# ExtensionConnector.net
KiCad netlist of a schematic drawn in Altium Designer
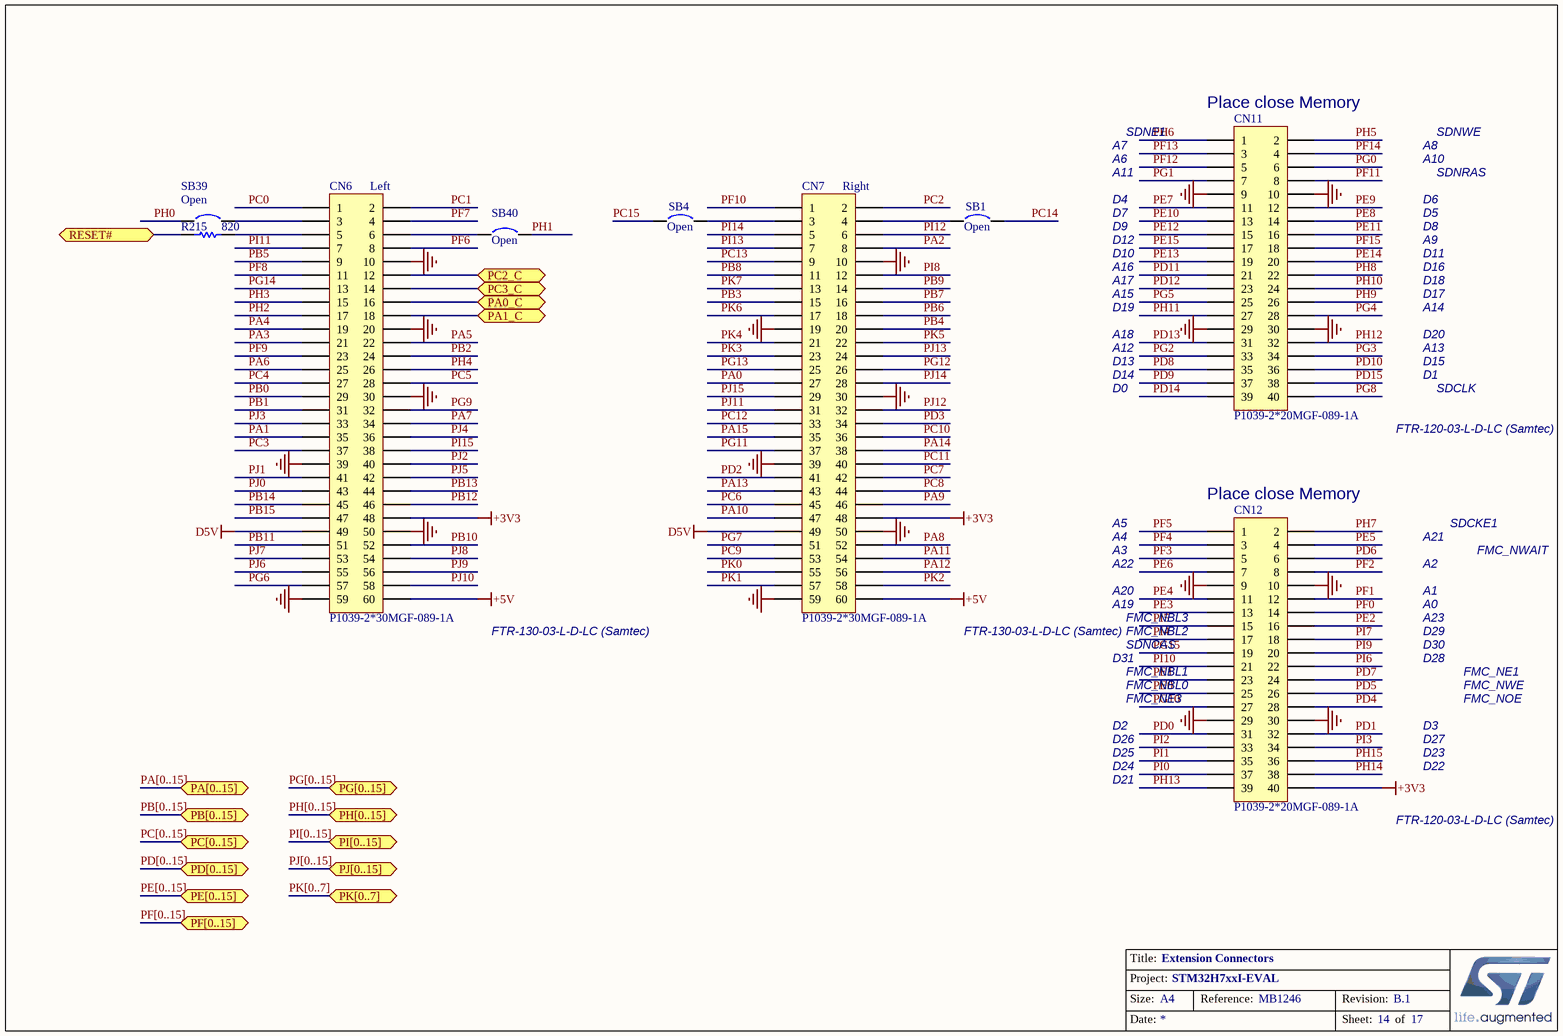
[diagram p0: ExtensionConnector.SchDoc]

(export (version "E")
  (design (tool "Eeschema 10.0.6"))
  (components
    (comp (ref "CN6")
      (value "P1039-2*30MGF-089-1A")
      (footprint "FTR-130-53-L-D-LC")
      (description "Header, 40-Pin, Dual row")
      (fields (field (name "PUBLISHER") "Altium Limited"))
      (libsource (lib "mb1045") (part "FTR-130-53-L-D-LC"))
    )
    (comp (ref "CN7")
      (value "P1039-2*30MGF-089-1A")
      (footprint "FTR-130-53-L-D-LC")
      (description "Header, 40-Pin, Dual row")
      (fields (field (name "PUBLISHER") "Altium Limited"))
      (libsource (lib "mb1045") (part "FTR-130-53-L-D-LC"))
    )
    (comp (ref "CN11")
      (value "P1039-2*20MGF-089-1A")
      (footprint "FTR-120-53-L-D-LC")
      (description "Header, 20-Pin, Dual row")
      (fields (field (name "PUBLISHER") "Altium Limited"))
      (libsource (lib "mb1045") (part "FTR-120-53-L-D-LC"))
    )
    (comp (ref "CN12")
      (value "P1039-2*20MGF-089-1A")
      (footprint "FTR-120-53-L-D-LC")
      (description "Header, 20-Pin, Dual row")
      (fields (field (name "PUBLISHER") "Altium Limited"))
      (libsource (lib "mb1045") (part "FTR-120-53-L-D-LC"))
    )
    (comp (ref "R215")
      (value "820")
      (footprint "0603R")
      (description "Resistor")
      (fields (field (name "PUBLISHER") "Altium Limited"))
      (libsource (lib "Miscellaneous Devices") (part "res1"))
    )
    (comp (ref "SB1")
      (value "Open")
      (footprint "0402R")
      (description "Circuit Breaker")
      (fields (field (name "PUBLISHER") "Altium Limited"))
      (libsource (lib "MB1167") (part "Circuit Breaker"))
    )
    (comp (ref "SB4")
      (value "Open")
      (footprint "0402R")
      (description "Circuit Breaker")
      (fields (field (name "PUBLISHER") "Altium Limited"))
      (libsource (lib "") (part "Circuit Breaker_1"))
    )
    (comp (ref "SB39")
      (value "Open")
      (footprint "SB_0603")
      (description "Circuit Breaker")
      (fields (field (name "PUBLISHER") "Altium Limited"))
      (libsource (lib "") (part "Circuit Breaker_1"))
    )
    (comp (ref "SB40")
      (value "Open")
      (footprint "SB_0603")
      (description "Circuit Breaker")
      (fields (field (name "PUBLISHER") "Altium Limited"))
      (libsource (lib "MB1167") (part "Circuit Breaker"))
    )
  )
  (nets
    (net (code "1") (name "+3V3") (class "Default")
      (node (ref "CN12") (pin "40") (pinfunction "40_40") (pintype "passive"))
      (node (ref "CN6") (pin "48") (pinfunction "48_48") (pintype "passive"))
      (node (ref "CN7") (pin "48") (pinfunction "48_48") (pintype "passive"))
    )
    (net (code "2") (name "+5V") (class "Default")
      (node (ref "CN6") (pin "60") (pinfunction "60_60") (pintype "passive"))
      (node (ref "CN7") (pin "60") (pinfunction "60_60") (pintype "passive"))
    )
    (net (code "3") (name "/PA0") (class "Default")
      (node (ref "CN7") (pin "27") (pinfunction "27_27") (pintype "passive"))
    )
    (net (code "4") (name "/PA0_C") (class "Default")
      (node (ref "CN6") (pin "16") (pinfunction "16_16") (pintype "passive"))
    )
    (net (code "5") (name "/PA1") (class "Default")
      (node (ref "CN6") (pin "35") (pinfunction "35_35") (pintype "passive"))
    )
    (net (code "6") (name "/PA1_C") (class "Default")
      (node (ref "CN6") (pin "18") (pinfunction "18_18") (pintype "passive"))
    )
    (net (code "7") (name "/PA2") (class "Default")
      (node (ref "CN7") (pin "8") (pinfunction "8_8") (pintype "passive"))
    )
    (net (code "8") (name "/PA3") (class "Default")
      (node (ref "CN6") (pin "21") (pinfunction "21_21") (pintype "passive"))
    )
    (net (code "9") (name "/PA4") (class "Default")
      (node (ref "CN6") (pin "19") (pinfunction "19_19") (pintype "passive"))
    )
    (net (code "10") (name "/PA5") (class "Default")
      (node (ref "CN6") (pin "22") (pinfunction "22_22") (pintype "passive"))
    )
    (net (code "11") (name "/PA6") (class "Default")
      (node (ref "CN6") (pin "25") (pinfunction "25_25") (pintype "passive"))
    )
    (net (code "12") (name "/PA7") (class "Default")
      (node (ref "CN6") (pin "34") (pinfunction "34_34") (pintype "passive"))
    )
    (net (code "13") (name "/PA8") (class "Default")
      (node (ref "CN7") (pin "52") (pinfunction "52_52") (pintype "passive"))
    )
    (net (code "14") (name "/PA9") (class "Default")
      (node (ref "CN7") (pin "46") (pinfunction "46_46") (pintype "passive"))
    )
    (net (code "15") (name "/PA10") (class "Default")
      (node (ref "CN7") (pin "47") (pinfunction "47_47") (pintype "passive"))
    )
    (net (code "16") (name "/PA11") (class "Default")
      (node (ref "CN7") (pin "54") (pinfunction "54_54") (pintype "passive"))
    )
    (net (code "17") (name "/PA12") (class "Default")
      (node (ref "CN7") (pin "56") (pinfunction "56_56") (pintype "passive"))
    )
    (net (code "18") (name "/PA13") (class "Default")
      (node (ref "CN7") (pin "43") (pinfunction "43_43") (pintype "passive"))
    )
    (net (code "19") (name "/PA14") (class "Default")
      (node (ref "CN7") (pin "38") (pinfunction "38_38") (pintype "passive"))
    )
    (net (code "20") (name "/PA15") (class "Default")
      (node (ref "CN7") (pin "35") (pinfunction "35_35") (pintype "passive"))
    )
    (net (code "22") (name "/PB0") (class "Default")
      (node (ref "CN6") (pin "29") (pinfunction "29_29") (pintype "passive"))
    )
    (net (code "23") (name "/PB1") (class "Default")
      (node (ref "CN6") (pin "31") (pinfunction "31_31") (pintype "passive"))
    )
    (net (code "24") (name "/PB2") (class "Default")
      (node (ref "CN6") (pin "24") (pinfunction "24_24") (pintype "passive"))
    )
    (net (code "25") (name "/PB3") (class "Default")
      (node (ref "CN7") (pin "15") (pinfunction "15_15") (pintype "passive"))
    )
    (net (code "26") (name "/PB4") (class "Default")
      (node (ref "CN7") (pin "20") (pinfunction "20_20") (pintype "passive"))
    )
    (net (code "27") (name "/PB5") (class "Default")
      (node (ref "CN6") (pin "9") (pinfunction "9_9") (pintype "passive"))
    )
    (net (code "28") (name "/PB6") (class "Default")
      (node (ref "CN7") (pin "18") (pinfunction "18_18") (pintype "passive"))
    )
    (net (code "29") (name "/PB7") (class "Default")
      (node (ref "CN7") (pin "16") (pinfunction "16_16") (pintype "passive"))
    )
    (net (code "30") (name "/PB8") (class "Default")
      (node (ref "CN7") (pin "11") (pinfunction "11_11") (pintype "passive"))
    )
    (net (code "31") (name "/PB9") (class "Default")
      (node (ref "CN7") (pin "14") (pinfunction "14_14") (pintype "passive"))
    )
    (net (code "32") (name "/PB10") (class "Default")
      (node (ref "CN6") (pin "52") (pinfunction "52_52") (pintype "passive"))
    )
    (net (code "33") (name "/PB11") (class "Default")
      (node (ref "CN6") (pin "51") (pinfunction "51_51") (pintype "passive"))
    )
    (net (code "34") (name "/PB12") (class "Default")
      (node (ref "CN6") (pin "46") (pinfunction "46_46") (pintype "passive"))
    )
    (net (code "35") (name "/PB13") (class "Default")
      (node (ref "CN6") (pin "44") (pinfunction "44_44") (pintype "passive"))
    )
    (net (code "36") (name "/PB14") (class "Default")
      (node (ref "CN6") (pin "45") (pinfunction "45_45") (pintype "passive"))
    )
    (net (code "37") (name "/PB15") (class "Default")
      (node (ref "CN6") (pin "47") (pinfunction "47_47") (pintype "passive"))
    )
    (net (code "39") (name "/PC0") (class "Default")
      (node (ref "CN6") (pin "1") (pinfunction "1_1") (pintype "passive"))
    )
    (net (code "40") (name "/PC1") (class "Default")
      (node (ref "CN6") (pin "2") (pinfunction "2_2") (pintype "passive"))
    )
    (net (code "41") (name "/PC2") (class "Default")
      (node (ref "CN7") (pin "2") (pinfunction "2_2") (pintype "passive"))
    )
    (net (code "42") (name "/PC2_C") (class "Default")
      (node (ref "CN6") (pin "12") (pinfunction "12_12") (pintype "passive"))
    )
    (net (code "43") (name "/PC3") (class "Default")
      (node (ref "CN6") (pin "37") (pinfunction "37_37") (pintype "passive"))
    )
    (net (code "44") (name "/PC3_C") (class "Default")
      (node (ref "CN6") (pin "14") (pinfunction "14_14") (pintype "passive"))
    )
    (net (code "45") (name "/PC4") (class "Default")
      (node (ref "CN6") (pin "27") (pinfunction "27_27") (pintype "passive"))
    )
    (net (code "46") (name "/PC5") (class "Default")
      (node (ref "CN6") (pin "28") (pinfunction "28_28") (pintype "passive"))
    )
    (net (code "47") (name "/PC6") (class "Default")
      (node (ref "CN7") (pin "45") (pinfunction "45_45") (pintype "passive"))
    )
    (net (code "48") (name "/PC7") (class "Default")
      (node (ref "CN7") (pin "42") (pinfunction "42_42") (pintype "passive"))
    )
    (net (code "49") (name "/PC8") (class "Default")
      (node (ref "CN7") (pin "44") (pinfunction "44_44") (pintype "passive"))
    )
    (net (code "50") (name "/PC9") (class "Default")
      (node (ref "CN7") (pin "53") (pinfunction "53_53") (pintype "passive"))
    )
    (net (code "51") (name "/PC10") (class "Default")
      (node (ref "CN7") (pin "36") (pinfunction "36_36") (pintype "passive"))
    )
    (net (code "52") (name "/PC11") (class "Default")
      (node (ref "CN7") (pin "40") (pinfunction "40_40") (pintype "passive"))
    )
    (net (code "53") (name "/PC12") (class "Default")
      (node (ref "CN7") (pin "33") (pinfunction "33_33") (pintype "passive"))
    )
    (net (code "54") (name "/PC13") (class "Default")
      (node (ref "CN7") (pin "9") (pinfunction "9_9") (pintype "passive"))
    )
    (net (code "55") (name "/PC14") (class "Default")
      (node (ref "SB1") (pin "1") (pinfunction "1_1") (pintype "passive"))
    )
    (net (code "56") (name "/PC15") (class "Default")
      (node (ref "SB4") (pin "1") (pinfunction "1_1") (pintype "passive"))
    )
    (net (code "58") (name "/PD0") (class "Default")
      (node (ref "CN12") (pin "31") (pinfunction "31_31") (pintype "passive"))
    )
    (net (code "59") (name "/PD1") (class "Default")
      (node (ref "CN12") (pin "32") (pinfunction "32_32") (pintype "passive"))
    )
    (net (code "60") (name "/PD2") (class "Default")
      (node (ref "CN7") (pin "41") (pinfunction "41_41") (pintype "passive"))
    )
    (net (code "61") (name "/PD3") (class "Default")
      (node (ref "CN7") (pin "34") (pinfunction "34_34") (pintype "passive"))
    )
    (net (code "62") (name "/PD4") (class "Default")
      (node (ref "CN12") (pin "28") (pinfunction "28_28") (pintype "passive"))
    )
    (net (code "63") (name "/PD5") (class "Default")
      (node (ref "CN12") (pin "26") (pinfunction "26_26") (pintype "passive"))
    )
    (net (code "64") (name "/PD6") (class "Default")
      (node (ref "CN12") (pin "6") (pinfunction "6_6") (pintype "passive"))
    )
    (net (code "65") (name "/PD7") (class "Default")
      (node (ref "CN12") (pin "24") (pinfunction "24_24") (pintype "passive"))
    )
    (net (code "66") (name "/PD8") (class "Default")
      (node (ref "CN11") (pin "35") (pinfunction "35_35") (pintype "passive"))
    )
    (net (code "67") (name "/PD9") (class "Default")
      (node (ref "CN11") (pin "37") (pinfunction "37_37") (pintype "passive"))
    )
    (net (code "68") (name "/PD10") (class "Default")
      (node (ref "CN11") (pin "36") (pinfunction "36_36") (pintype "passive"))
    )
    (net (code "69") (name "/PD11") (class "Default")
      (node (ref "CN11") (pin "21") (pinfunction "21_21") (pintype "passive"))
    )
    (net (code "70") (name "/PD12") (class "Default")
      (node (ref "CN11") (pin "23") (pinfunction "23_23") (pintype "passive"))
    )
    (net (code "71") (name "/PD13") (class "Default")
      (node (ref "CN11") (pin "31") (pinfunction "31_31") (pintype "passive"))
    )
    (net (code "72") (name "/PD14") (class "Default")
      (node (ref "CN11") (pin "39") (pinfunction "39_39") (pintype "passive"))
    )
    (net (code "73") (name "/PD15") (class "Default")
      (node (ref "CN11") (pin "38") (pinfunction "38_38") (pintype "passive"))
    )
    (net (code "75") (name "/PE0") (class "Default")
      (node (ref "CN12") (pin "25") (pinfunction "25_25") (pintype "passive"))
    )
    (net (code "76") (name "/PE1") (class "Default")
      (node (ref "CN12") (pin "23") (pinfunction "23_23") (pintype "passive"))
    )
    (net (code "77") (name "/PE2") (class "Default")
      (node (ref "CN12") (pin "16") (pinfunction "16_16") (pintype "passive"))
    )
    (net (code "78") (name "/PE3") (class "Default")
      (node (ref "CN12") (pin "13") (pinfunction "13_13") (pintype "passive"))
    )
    (net (code "79") (name "/PE4") (class "Default")
      (node (ref "CN12") (pin "11") (pinfunction "11_11") (pintype "passive"))
    )
    (net (code "80") (name "/PE5") (class "Default")
      (node (ref "CN12") (pin "4") (pinfunction "4_4") (pintype "passive"))
    )
    (net (code "81") (name "/PE6") (class "Default")
      (node (ref "CN12") (pin "7") (pinfunction "7_7") (pintype "passive"))
    )
    (net (code "82") (name "/PE7") (class "Default")
      (node (ref "CN11") (pin "11") (pinfunction "11_11") (pintype "passive"))
    )
    (net (code "83") (name "/PE8") (class "Default")
      (node (ref "CN11") (pin "14") (pinfunction "14_14") (pintype "passive"))
    )
    (net (code "84") (name "/PE9") (class "Default")
      (node (ref "CN11") (pin "12") (pinfunction "12_12") (pintype "passive"))
    )
    (net (code "85") (name "/PE10") (class "Default")
      (node (ref "CN11") (pin "13") (pinfunction "13_13") (pintype "passive"))
    )
    (net (code "86") (name "/PE11") (class "Default")
      (node (ref "CN11") (pin "16") (pinfunction "16_16") (pintype "passive"))
    )
    (net (code "87") (name "/PE12") (class "Default")
      (node (ref "CN11") (pin "15") (pinfunction "15_15") (pintype "passive"))
    )
    (net (code "88") (name "/PE13") (class "Default")
      (node (ref "CN11") (pin "19") (pinfunction "19_19") (pintype "passive"))
    )
    (net (code "89") (name "/PE14") (class "Default")
      (node (ref "CN11") (pin "20") (pinfunction "20_20") (pintype "passive"))
    )
    (net (code "90") (name "/PE15") (class "Default")
      (node (ref "CN11") (pin "17") (pinfunction "17_17") (pintype "passive"))
    )
    (net (code "92") (name "/PF0") (class "Default")
      (node (ref "CN12") (pin "14") (pinfunction "14_14") (pintype "passive"))
    )
    (net (code "93") (name "/PF1") (class "Default")
      (node (ref "CN12") (pin "12") (pinfunction "12_12") (pintype "passive"))
    )
    (net (code "94") (name "/PF2") (class "Default")
      (node (ref "CN12") (pin "8") (pinfunction "8_8") (pintype "passive"))
    )
    (net (code "95") (name "/PF3") (class "Default")
      (node (ref "CN12") (pin "5") (pinfunction "5_5") (pintype "passive"))
    )
    (net (code "96") (name "/PF4") (class "Default")
      (node (ref "CN12") (pin "3") (pinfunction "3_3") (pintype "passive"))
    )
    (net (code "97") (name "/PF5") (class "Default")
      (node (ref "CN12") (pin "1") (pinfunction "1_1") (pintype "passive"))
    )
    (net (code "98") (name "/PF6") (class "Default")
      (node (ref "CN6") (pin "8") (pinfunction "8_8") (pintype "passive"))
    )
    (net (code "99") (name "/PF7") (class "Default")
      (node (ref "CN6") (pin "4") (pinfunction "4_4") (pintype "passive"))
    )
    (net (code "100") (name "/PF8") (class "Default")
      (node (ref "CN6") (pin "11") (pinfunction "11_11") (pintype "passive"))
    )
    (net (code "101") (name "/PF9") (class "Default")
      (node (ref "CN6") (pin "23") (pinfunction "23_23") (pintype "passive"))
    )
    (net (code "102") (name "/PF10") (class "Default")
      (node (ref "CN7") (pin "1") (pinfunction "1_1") (pintype "passive"))
    )
    (net (code "103") (name "/PF11") (class "Default")
      (node (ref "CN11") (pin "8") (pinfunction "8_8") (pintype "passive"))
    )
    (net (code "104") (name "/PF12") (class "Default")
      (node (ref "CN11") (pin "5") (pinfunction "5_5") (pintype "passive"))
    )
    (net (code "105") (name "/PF13") (class "Default")
      (node (ref "CN11") (pin "3") (pinfunction "3_3") (pintype "passive"))
    )
    (net (code "106") (name "/PF14") (class "Default")
      (node (ref "CN11") (pin "4") (pinfunction "4_4") (pintype "passive"))
    )
    (net (code "107") (name "/PF15") (class "Default")
      (node (ref "CN11") (pin "18") (pinfunction "18_18") (pintype "passive"))
    )
    (net (code "109") (name "/PG0") (class "Default")
      (node (ref "CN11") (pin "6") (pinfunction "6_6") (pintype "passive"))
    )
    (net (code "110") (name "/PG1") (class "Default")
      (node (ref "CN11") (pin "7") (pinfunction "7_7") (pintype "passive"))
    )
    (net (code "111") (name "/PG2") (class "Default")
      (node (ref "CN11") (pin "33") (pinfunction "33_33") (pintype "passive"))
    )
    (net (code "112") (name "/PG3") (class "Default")
      (node (ref "CN11") (pin "34") (pinfunction "34_34") (pintype "passive"))
    )
    (net (code "113") (name "/PG4") (class "Default")
      (node (ref "CN11") (pin "28") (pinfunction "28_28") (pintype "passive"))
    )
    (net (code "114") (name "/PG5") (class "Default")
      (node (ref "CN11") (pin "25") (pinfunction "25_25") (pintype "passive"))
    )
    (net (code "115") (name "/PG6") (class "Default")
      (node (ref "CN6") (pin "57") (pinfunction "57_57") (pintype "passive"))
    )
    (net (code "116") (name "/PG7") (class "Default")
      (node (ref "CN7") (pin "51") (pinfunction "51_51") (pintype "passive"))
    )
    (net (code "117") (name "/PG8") (class "Default")
      (node (ref "CN11") (pin "40") (pinfunction "40_40") (pintype "passive"))
    )
    (net (code "118") (name "/PG9") (class "Default")
      (node (ref "CN6") (pin "32") (pinfunction "32_32") (pintype "passive"))
    )
    (net (code "119") (name "/PG10") (class "Default")
      (node (ref "CN12") (pin "27") (pinfunction "27_27") (pintype "passive"))
    )
    (net (code "120") (name "/PG11") (class "Default")
      (node (ref "CN7") (pin "37") (pinfunction "37_37") (pintype "passive"))
    )
    (net (code "121") (name "/PG12") (class "Default")
      (node (ref "CN7") (pin "26") (pinfunction "26_26") (pintype "passive"))
    )
    (net (code "122") (name "/PG13") (class "Default")
      (node (ref "CN7") (pin "25") (pinfunction "25_25") (pintype "passive"))
    )
    (net (code "123") (name "/PG14") (class "Default")
      (node (ref "CN6") (pin "13") (pinfunction "13_13") (pintype "passive"))
    )
    (net (code "124") (name "/PG15") (class "Default")
      (node (ref "CN12") (pin "19") (pinfunction "19_19") (pintype "passive"))
    )
    (net (code "126") (name "/PH0") (class "Default")
      (node (ref "SB39") (pin "1") (pinfunction "1_1") (pintype "passive"))
    )
    (net (code "127") (name "/PH1") (class "Default")
      (node (ref "SB40") (pin "1") (pinfunction "1_1") (pintype "passive"))
    )
    (net (code "128") (name "/PH2") (class "Default")
      (node (ref "CN6") (pin "17") (pinfunction "17_17") (pintype "passive"))
    )
    (net (code "129") (name "/PH3") (class "Default")
      (node (ref "CN6") (pin "15") (pinfunction "15_15") (pintype "passive"))
    )
    (net (code "130") (name "/PH4") (class "Default")
      (node (ref "CN6") (pin "26") (pinfunction "26_26") (pintype "passive"))
    )
    (net (code "131") (name "/PH5") (class "Default")
      (node (ref "CN11") (pin "2") (pinfunction "2_2") (pintype "passive"))
    )
    (net (code "132") (name "/PH6") (class "Default")
      (node (ref "CN11") (pin "1") (pinfunction "1_1") (pintype "passive"))
    )
    (net (code "133") (name "/PH7") (class "Default")
      (node (ref "CN12") (pin "2") (pinfunction "2_2") (pintype "passive"))
    )
    (net (code "134") (name "/PH8") (class "Default")
      (node (ref "CN11") (pin "22") (pinfunction "22_22") (pintype "passive"))
    )
    (net (code "135") (name "/PH9") (class "Default")
      (node (ref "CN11") (pin "26") (pinfunction "26_26") (pintype "passive"))
    )
    (net (code "136") (name "/PH10") (class "Default")
      (node (ref "CN11") (pin "24") (pinfunction "24_24") (pintype "passive"))
    )
    (net (code "137") (name "/PH11") (class "Default")
      (node (ref "CN11") (pin "27") (pinfunction "27_27") (pintype "passive"))
    )
    (net (code "138") (name "/PH12") (class "Default")
      (node (ref "CN11") (pin "32") (pinfunction "32_32") (pintype "passive"))
    )
    (net (code "139") (name "/PH13") (class "Default")
      (node (ref "CN12") (pin "39") (pinfunction "39_39") (pintype "passive"))
    )
    (net (code "140") (name "/PH14") (class "Default")
      (node (ref "CN12") (pin "38") (pinfunction "38_38") (pintype "passive"))
    )
    (net (code "141") (name "/PH15") (class "Default")
      (node (ref "CN12") (pin "36") (pinfunction "36_36") (pintype "passive"))
    )
    (net (code "143") (name "/PI0") (class "Default")
      (node (ref "CN12") (pin "37") (pinfunction "37_37") (pintype "passive"))
    )
    (net (code "144") (name "/PI1") (class "Default")
      (node (ref "CN12") (pin "35") (pinfunction "35_35") (pintype "passive"))
    )
    (net (code "145") (name "/PI2") (class "Default")
      (node (ref "CN12") (pin "33") (pinfunction "33_33") (pintype "passive"))
    )
    (net (code "146") (name "/PI3") (class "Default")
      (node (ref "CN12") (pin "34") (pinfunction "34_34") (pintype "passive"))
    )
    (net (code "147") (name "/PI4") (class "Default")
      (node (ref "CN12") (pin "17") (pinfunction "17_17") (pintype "passive"))
    )
    (net (code "148") (name "/PI5") (class "Default")
      (node (ref "CN12") (pin "15") (pinfunction "15_15") (pintype "passive"))
    )
    (net (code "149") (name "/PI6") (class "Default")
      (node (ref "CN12") (pin "22") (pinfunction "22_22") (pintype "passive"))
    )
    (net (code "150") (name "/PI7") (class "Default")
      (node (ref "CN12") (pin "18") (pinfunction "18_18") (pintype "passive"))
    )
    (net (code "151") (name "/PI8") (class "Default")
      (node (ref "CN7") (pin "12") (pinfunction "12_12") (pintype "passive"))
    )
    (net (code "152") (name "/PI9") (class "Default")
      (node (ref "CN12") (pin "20") (pinfunction "20_20") (pintype "passive"))
    )
    (net (code "153") (name "/PI10") (class "Default")
      (node (ref "CN12") (pin "21") (pinfunction "21_21") (pintype "passive"))
    )
    (net (code "154") (name "/PI11") (class "Default")
      (node (ref "CN6") (pin "7") (pinfunction "7_7") (pintype "passive"))
    )
    (net (code "155") (name "/PI12") (class "Default")
      (node (ref "CN7") (pin "6") (pinfunction "6_6") (pintype "passive"))
    )
    (net (code "156") (name "/PI13") (class "Default")
      (node (ref "CN7") (pin "7") (pinfunction "7_7") (pintype "passive"))
    )
    (net (code "157") (name "/PI14") (class "Default")
      (node (ref "CN7") (pin "5") (pinfunction "5_5") (pintype "passive"))
    )
    (net (code "158") (name "/PI15") (class "Default")
      (node (ref "CN6") (pin "38") (pinfunction "38_38") (pintype "passive"))
    )
    (net (code "160") (name "/PJ0") (class "Default")
      (node (ref "CN6") (pin "43") (pinfunction "43_43") (pintype "passive"))
    )
    (net (code "161") (name "/PJ1") (class "Default")
      (node (ref "CN6") (pin "41") (pinfunction "41_41") (pintype "passive"))
    )
    (net (code "162") (name "/PJ2") (class "Default")
      (node (ref "CN6") (pin "40") (pinfunction "40_40") (pintype "passive"))
    )
    (net (code "163") (name "/PJ3") (class "Default")
      (node (ref "CN6") (pin "33") (pinfunction "33_33") (pintype "passive"))
    )
    (net (code "164") (name "/PJ4") (class "Default")
      (node (ref "CN6") (pin "36") (pinfunction "36_36") (pintype "passive"))
    )
    (net (code "165") (name "/PJ5") (class "Default")
      (node (ref "CN6") (pin "42") (pinfunction "42_42") (pintype "passive"))
    )
    (net (code "166") (name "/PJ6") (class "Default")
      (node (ref "CN6") (pin "55") (pinfunction "55_55") (pintype "passive"))
    )
    (net (code "167") (name "/PJ7") (class "Default")
      (node (ref "CN6") (pin "53") (pinfunction "53_53") (pintype "passive"))
    )
    (net (code "168") (name "/PJ8") (class "Default")
      (node (ref "CN6") (pin "54") (pinfunction "54_54") (pintype "passive"))
    )
    (net (code "169") (name "/PJ9") (class "Default")
      (node (ref "CN6") (pin "56") (pinfunction "56_56") (pintype "passive"))
    )
    (net (code "170") (name "/PJ10") (class "Default")
      (node (ref "CN6") (pin "58") (pinfunction "58_58") (pintype "passive"))
    )
    (net (code "171") (name "/PJ11") (class "Default")
      (node (ref "CN7") (pin "31") (pinfunction "31_31") (pintype "passive"))
    )
    (net (code "172") (name "/PJ12") (class "Default")
      (node (ref "CN7") (pin "32") (pinfunction "32_32") (pintype "passive"))
    )
    (net (code "173") (name "/PJ13") (class "Default")
      (node (ref "CN7") (pin "24") (pinfunction "24_24") (pintype "passive"))
    )
    (net (code "174") (name "/PJ14") (class "Default")
      (node (ref "CN7") (pin "28") (pinfunction "28_28") (pintype "passive"))
    )
    (net (code "175") (name "/PJ15") (class "Default")
      (node (ref "CN7") (pin "29") (pinfunction "29_29") (pintype "passive"))
    )
    (net (code "177") (name "/PK0") (class "Default")
      (node (ref "CN7") (pin "55") (pinfunction "55_55") (pintype "passive"))
    )
    (net (code "178") (name "/PK1") (class "Default")
      (node (ref "CN7") (pin "57") (pinfunction "57_57") (pintype "passive"))
    )
    (net (code "179") (name "/PK2") (class "Default")
      (node (ref "CN7") (pin "58") (pinfunction "58_58") (pintype "passive"))
    )
    (net (code "180") (name "/PK3") (class "Default")
      (node (ref "CN7") (pin "23") (pinfunction "23_23") (pintype "passive"))
    )
    (net (code "181") (name "/PK4") (class "Default")
      (node (ref "CN7") (pin "21") (pinfunction "21_21") (pintype "passive"))
    )
    (net (code "182") (name "/PK5") (class "Default")
      (node (ref "CN7") (pin "22") (pinfunction "22_22") (pintype "passive"))
    )
    (net (code "183") (name "/PK6") (class "Default")
      (node (ref "CN7") (pin "17") (pinfunction "17_17") (pintype "passive"))
    )
    (net (code "184") (name "/PK7") (class "Default")
      (node (ref "CN7") (pin "13") (pinfunction "13_13") (pintype "passive"))
    )
    (net (code "186") (name "/RESET#") (class "Default")
      (node (ref "R215") (pin "1") (pinfunction "1_1") (pintype "passive"))
    )
    (net (code "187") (name "D5V") (class "Default")
      (node (ref "CN6") (pin "49") (pinfunction "49_49") (pintype "passive"))
      (node (ref "CN7") (pin "49") (pinfunction "49_49") (pintype "passive"))
    )
    (net (code "188") (name "GND") (class "Default")
      (node (ref "CN11") (pin "10") (pinfunction "10_10") (pintype "passive"))
      (node (ref "CN11") (pin "29") (pinfunction "29_29") (pintype "passive"))
      (node (ref "CN11") (pin "30") (pinfunction "30_30") (pintype "passive"))
      (node (ref "CN11") (pin "9") (pinfunction "9_9") (pintype "passive"))
      (node (ref "CN12") (pin "10") (pinfunction "10_10") (pintype "passive"))
      (node (ref "CN12") (pin "29") (pinfunction "29_29") (pintype "passive"))
      (node (ref "CN12") (pin "30") (pinfunction "30_30") (pintype "passive"))
      (node (ref "CN12") (pin "9") (pinfunction "9_9") (pintype "passive"))
      (node (ref "CN6") (pin "10") (pinfunction "10_10") (pintype "passive"))
      (node (ref "CN6") (pin "20") (pinfunction "20_20") (pintype "passive"))
      (node (ref "CN6") (pin "30") (pinfunction "30_30") (pintype "passive"))
      (node (ref "CN6") (pin "39") (pinfunction "39_39") (pintype "passive"))
      (node (ref "CN6") (pin "50") (pinfunction "50_50") (pintype "passive"))
      (node (ref "CN6") (pin "59") (pinfunction "59_59") (pintype "passive"))
      (node (ref "CN7") (pin "10") (pinfunction "10_10") (pintype "passive"))
      (node (ref "CN7") (pin "19") (pinfunction "19_19") (pintype "passive"))
      (node (ref "CN7") (pin "30") (pinfunction "30_30") (pintype "passive"))
      (node (ref "CN7") (pin "39") (pinfunction "39_39") (pintype "passive"))
      (node (ref "CN7") (pin "50") (pinfunction "50_50") (pintype "passive"))
      (node (ref "CN7") (pin "59") (pinfunction "59_59") (pintype "passive"))
    )
    (net (code "189") (name "Net-(CN6-Pad3)") (class "Default")
      (node (ref "CN6") (pin "3") (pinfunction "3_3") (pintype "passive"))
      (node (ref "SB39") (pin "2") (pinfunction "2_2") (pintype "passive"))
    )
    (net (code "190") (name "Net-(CN6-Pad5)") (class "Default")
      (node (ref "CN6") (pin "5") (pinfunction "5_5") (pintype "passive"))
      (node (ref "R215") (pin "2") (pinfunction "2_2") (pintype "passive"))
    )
    (net (code "191") (name "Net-(CN6-Pad6)") (class "Default")
      (node (ref "CN6") (pin "6") (pinfunction "6_6") (pintype "passive"))
      (node (ref "SB40") (pin "2") (pinfunction "2_2") (pintype "passive"))
    )
    (net (code "192") (name "Net-(CN7-Pad3)") (class "Default")
      (node (ref "CN7") (pin "3") (pinfunction "3_3") (pintype "passive"))
      (node (ref "SB4") (pin "2") (pinfunction "2_2") (pintype "passive"))
    )
    (net (code "193") (name "Net-(CN7-Pad4)") (class "Default")
      (node (ref "CN7") (pin "4") (pinfunction "4_4") (pintype "passive"))
      (node (ref "SB1") (pin "2") (pinfunction "2_2") (pintype "passive"))
    )
  )
)
